# QXZ-v1_0.net
KiCad netlist of a schematic drawn in Altium Designer
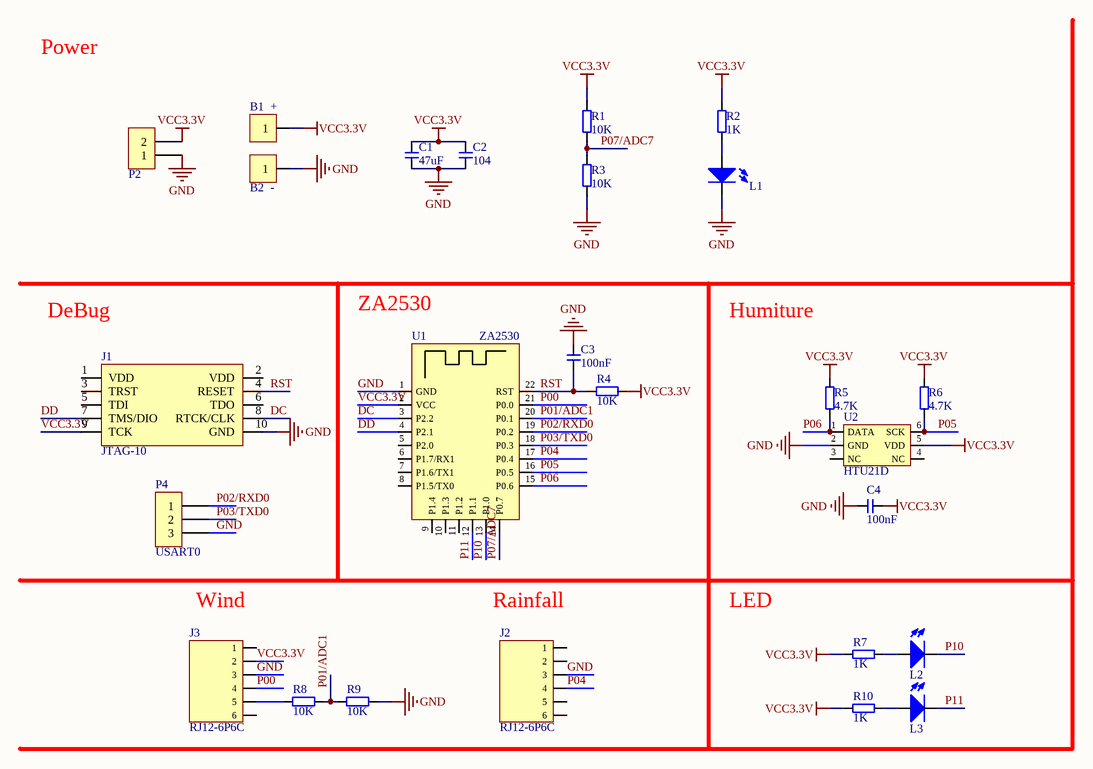
[diagram p0: QXZ-v1.0.SchDoc]

(export (version "E")
  (design (tool "Eeschema 10.0.6"))
  (components
    (comp (ref "B1")
      (value "+")
      (footprint "BatteryContacts-5#")
      (libsource (lib "集成库1") (part "BatteryContacts-5#"))
    )
    (comp (ref "B2")
      (value "-")
      (footprint "BatteryContacts-5#")
      (libsource (lib "集成库1") (part "BatteryContacts-5#"))
    )
    (comp (ref "C1") (value "47uF") (footprint "CAP(0805)") (libsource (lib "集成库1") (part "Cap0805")))
    (comp (ref "C2") (value "104") (footprint "CAP(0603)") (libsource (lib "集成库1") (part "Cap0603")))
    (comp (ref "C3") (value "100nF") (footprint "CAP(0603)") (libsource (lib "集成库1") (part "Cap0603")))
    (comp (ref "C4") (value "100nF") (footprint "CAP(0603)") (libsource (lib "集成库1") (part "Cap0603")))
    (comp (ref "J1") (value "JTAG-10") (footprint "JTAG-10") (libsource (lib "集成库1") (part "JTAG-10")))
    (comp (ref "J2")
      (value "RJ12-6P6C")
      (footprint "RJ12-6P6C-up")
      (libsource (lib "集成库1") (part "RJ12-6P6C-up"))
    )
    (comp (ref "J3")
      (value "RJ12-6P6C")
      (footprint "RJ12-6P6C-up")
      (libsource (lib "集成库1") (part "RJ12-6P6C-up"))
    )
    (comp (ref "L1") (value "LED") (footprint "led0805") (libsource (lib "集成库1") (part "LED0805")))
    (comp (ref "L2") (value "LED") (footprint "led0805") (libsource (lib "集成库1") (part "LED0805")))
    (comp (ref "L3") (value "LED") (footprint "led0805") (libsource (lib "集成库1") (part "LED0805")))
    (comp (ref "P2") (value "Header2") (footprint "Header2") (libsource (lib "集成库1") (part "Header2")))
    (comp (ref "P4") (value "USART0") (footprint "HEADER3") (libsource (lib "集成库1") (part "Header3")))
    (comp (ref "R1") (value "10K") (footprint "RES0603") (libsource (lib "集成库1") (part "RES0603")))
    (comp (ref "R2") (value "1K") (footprint "RES0603") (libsource (lib "集成库1") (part "RES0603")))
    (comp (ref "R3") (value "10K") (footprint "RES0603") (libsource (lib "集成库1") (part "RES0603")))
    (comp (ref "R4") (value "10K") (footprint "RES0603") (libsource (lib "") (part "RES0603_1")))
    (comp (ref "R5") (value "4.7K") (footprint "RES0603") (libsource (lib "集成库1") (part "RES0603")))
    (comp (ref "R6") (value "4.7K") (footprint "RES0603") (libsource (lib "集成库1") (part "RES0603")))
    (comp (ref "R7") (value "1K") (footprint "RES0603") (libsource (lib "") (part "RES0603_1")))
    (comp (ref "R8") (value "10K") (footprint "RES0603") (libsource (lib "") (part "RES0603_1")))
    (comp (ref "R9") (value "10K") (footprint "RES0603") (libsource (lib "") (part "RES0603_1")))
    (comp (ref "R10") (value "1K") (footprint "RES0603") (libsource (lib "") (part "RES0603_1")))
    (comp (ref "U1") (value "ZA2530") (footprint "ZA2530A") (libsource (lib "集成库1") (part "ZA2530A")))
    (comp (ref "U2") (value "HTU21D") (footprint "DFN6") (libsource (lib "集成库1") (part "htu21d")))
  )
  (nets
    (net (code "1") (name "/DC") (class "Default")
      (node (ref "J1") (pin "8") (pinfunction "RTCK/CLK_8") (pintype "passive"))
      (node (ref "U1") (pin "3") (pinfunction "P2.2_3") (pintype "passive"))
    )
    (net (code "2") (name "/DD") (class "Default")
      (node (ref "J1") (pin "7") (pinfunction "TMS/DIO_7") (pintype "passive"))
      (node (ref "U1") (pin "4") (pinfunction "P2.1_4") (pintype "passive"))
    )
    (net (code "3") (name "/P00") (class "Default")
      (node (ref "J3") (pin "4") (pinfunction "4_4") (pintype "passive"))
      (node (ref "U1") (pin "21") (pinfunction "P0.0_21") (pintype "passive"))
    )
    (net (code "4") (name "/P01{slash}ADC1") (class "Default")
      (node (ref "R8") (pin "2") (pinfunction "2_2") (pintype "passive"))
      (node (ref "R9") (pin "1") (pinfunction "1_1") (pintype "passive"))
      (node (ref "U1") (pin "20") (pinfunction "P0.1_20") (pintype "passive"))
    )
    (net (code "5") (name "/P02{slash}RXD0") (class "Default")
      (node (ref "P4") (pin "1") (pinfunction "1_1") (pintype "passive"))
      (node (ref "U1") (pin "19") (pinfunction "P0.2_19") (pintype "passive"))
    )
    (net (code "6") (name "/P03{slash}TXD0") (class "Default")
      (node (ref "P4") (pin "2") (pinfunction "2_2") (pintype "passive"))
      (node (ref "U1") (pin "18") (pinfunction "P0.3_18") (pintype "passive"))
    )
    (net (code "7") (name "/P04") (class "Default")
      (node (ref "J2") (pin "4") (pinfunction "4_4") (pintype "passive"))
      (node (ref "U1") (pin "17") (pinfunction "P0.4_17") (pintype "passive"))
    )
    (net (code "8") (name "/P05") (class "Default")
      (node (ref "R6") (pin "1") (pinfunction "1_1") (pintype "passive"))
      (node (ref "U1") (pin "16") (pinfunction "P0.5_16") (pintype "passive"))
      (node (ref "U2") (pin "6") (pinfunction "SCK_6") (pintype "passive"))
    )
    (net (code "9") (name "/P06") (class "Default")
      (node (ref "R5") (pin "1") (pinfunction "1_1") (pintype "passive"))
      (node (ref "U1") (pin "15") (pinfunction "P0.6_15") (pintype "passive"))
      (node (ref "U2") (pin "1") (pinfunction "DATA_1") (pintype "passive"))
    )
    (net (code "10") (name "/P07{slash}ADC7") (class "Default")
      (node (ref "R1") (pin "1") (pinfunction "1_1") (pintype "passive"))
      (node (ref "R3") (pin "2") (pinfunction "2_2") (pintype "passive"))
      (node (ref "U1") (pin "14") (pinfunction "P0.7_14") (pintype "passive"))
    )
    (net (code "11") (name "/P10") (class "Default")
      (node (ref "L2") (pin "2") (pinfunction "2_2") (pintype "passive"))
      (node (ref "U1") (pin "13") (pinfunction "P1.0_13") (pintype "passive"))
    )
    (net (code "12") (name "/P11") (class "Default")
      (node (ref "L3") (pin "2") (pinfunction "2_2") (pintype "passive"))
      (node (ref "U1") (pin "12") (pinfunction "P1.1_12") (pintype "passive"))
    )
    (net (code "13") (name "/RST") (class "Default")
      (node (ref "C3") (pin "1") (pinfunction "1_1") (pintype "passive"))
      (node (ref "J1") (pin "4") (pinfunction "RESET_4") (pintype "passive"))
      (node (ref "R4") (pin "1") (pinfunction "1_1") (pintype "passive"))
      (node (ref "U1") (pin "22") (pinfunction "RST_22") (pintype "passive"))
    )
    (net (code "14") (name "GND") (class "Default")
      (node (ref "B2") (pin "1") (pinfunction "1_1") (pintype "passive"))
      (node (ref "C1") (pin "1") (pinfunction "1_1") (pintype "passive"))
      (node (ref "C2") (pin "1") (pinfunction "1_1") (pintype "passive"))
      (node (ref "C3") (pin "2") (pinfunction "2_2") (pintype "passive"))
      (node (ref "C4") (pin "1") (pinfunction "1_1") (pintype "passive"))
      (node (ref "J1") (pin "10") (pinfunction "GND_10") (pintype "passive"))
      (node (ref "J2") (pin "3") (pinfunction "3_3") (pintype "passive"))
      (node (ref "J3") (pin "3") (pinfunction "3_3") (pintype "passive"))
      (node (ref "L1") (pin "2") (pinfunction "2_2") (pintype "passive"))
      (node (ref "P2") (pin "1") (pinfunction "1_1") (pintype "passive"))
      (node (ref "P4") (pin "3") (pinfunction "3_3") (pintype "passive"))
      (node (ref "R3") (pin "1") (pinfunction "1_1") (pintype "passive"))
      (node (ref "R9") (pin "2") (pinfunction "2_2") (pintype "passive"))
      (node (ref "U1") (pin "1") (pinfunction "GND_1") (pintype "passive"))
      (node (ref "U2") (pin "2") (pinfunction "GND_2") (pintype "passive"))
    )
    (net (code "15") (name "Net-(J3-Pad5)") (class "Default")
      (node (ref "J3") (pin "5") (pinfunction "5_5") (pintype "passive"))
      (node (ref "R8") (pin "1") (pinfunction "1_1") (pintype "passive"))
    )
    (net (code "16") (name "Net-(L1-Pad1)") (class "Default")
      (node (ref "L1") (pin "1") (pinfunction "1_1") (pintype "passive"))
      (node (ref "R2") (pin "1") (pinfunction "1_1") (pintype "passive"))
    )
    (net (code "17") (name "Net-(L2-Pad1)") (class "Default")
      (node (ref "L2") (pin "1") (pinfunction "1_1") (pintype "passive"))
      (node (ref "R7") (pin "2") (pinfunction "2_2") (pintype "passive"))
    )
    (net (code "18") (name "Net-(L3-Pad1)") (class "Default")
      (node (ref "L3") (pin "1") (pinfunction "1_1") (pintype "passive"))
      (node (ref "R10") (pin "2") (pinfunction "2_2") (pintype "passive"))
    )
    (net (code "19") (name "VCC3.3V") (class "Default")
      (node (ref "B1") (pin "1") (pinfunction "1_1") (pintype "passive"))
      (node (ref "C1") (pin "2") (pinfunction "2_2") (pintype "passive"))
      (node (ref "C2") (pin "2") (pinfunction "2_2") (pintype "passive"))
      (node (ref "C4") (pin "2") (pinfunction "2_2") (pintype "passive"))
      (node (ref "J1") (pin "9") (pinfunction "TCK_9") (pintype "passive"))
      (node (ref "J3") (pin "2") (pinfunction "2_2") (pintype "passive"))
      (node (ref "P2") (pin "2") (pinfunction "2_2") (pintype "passive"))
      (node (ref "R1") (pin "2") (pinfunction "2_2") (pintype "passive"))
      (node (ref "R10") (pin "1") (pinfunction "1_1") (pintype "passive"))
      (node (ref "R2") (pin "2") (pinfunction "2_2") (pintype "passive"))
      (node (ref "R4") (pin "2") (pinfunction "2_2") (pintype "passive"))
      (node (ref "R5") (pin "2") (pinfunction "2_2") (pintype "passive"))
      (node (ref "R6") (pin "2") (pinfunction "2_2") (pintype "passive"))
      (node (ref "R7") (pin "1") (pinfunction "1_1") (pintype "passive"))
      (node (ref "U1") (pin "2") (pinfunction "VCC_2") (pintype "passive"))
      (node (ref "U2") (pin "5") (pinfunction "VDD_5") (pintype "passive"))
    )
    (net (code "20") (name "unconnected-(J1-TDI-Pad5)") (class "Default")
      (node (ref "J1") (pin "5") (pinfunction "TDI_5") (pintype "passive"))
    )
    (net (code "21") (name "unconnected-(J1-TDO-Pad6)") (class "Default")
      (node (ref "J1") (pin "6") (pinfunction "TDO_6") (pintype "passive"))
    )
    (net (code "22") (name "unconnected-(J1-TRST-Pad3)") (class "Default")
      (node (ref "J1") (pin "3") (pinfunction "TRST_3") (pintype "passive"))
    )
    (net (code "23") (name "unconnected-(J1-VDD-Pad1)") (class "Default")
      (node (ref "J1") (pin "1") (pinfunction "VDD_1") (pintype "passive"))
    )
    (net (code "24") (name "unconnected-(J1-VDD-Pad2)") (class "Default")
      (node (ref "J1") (pin "2") (pinfunction "VDD_2") (pintype "passive"))
    )
    (net (code "25") (name "unconnected-(J2-Pad1)") (class "Default")
      (node (ref "J2") (pin "1") (pinfunction "1_1") (pintype "passive"))
    )
    (net (code "26") (name "unconnected-(J2-Pad2)") (class "Default")
      (node (ref "J2") (pin "2") (pinfunction "2_2") (pintype "passive"))
    )
    (net (code "27") (name "unconnected-(J2-Pad5)") (class "Default")
      (node (ref "J2") (pin "5") (pinfunction "5_5") (pintype "passive"))
    )
    (net (code "28") (name "unconnected-(J2-Pad6)") (class "Default")
      (node (ref "J2") (pin "6") (pinfunction "6_6") (pintype "passive"))
    )
    (net (code "29") (name "unconnected-(J3-Pad1)") (class "Default")
      (node (ref "J3") (pin "1") (pinfunction "1_1") (pintype "passive"))
    )
    (net (code "30") (name "unconnected-(J3-Pad6)") (class "Default")
      (node (ref "J3") (pin "6") (pinfunction "6_6") (pintype "passive"))
    )
    (net (code "31") (name "unconnected-(U1-P1.2-Pad11)") (class "Default")
      (node (ref "U1") (pin "11") (pinfunction "P1.2_11") (pintype "passive"))
    )
    (net (code "32") (name "unconnected-(U1-P1.3-Pad10)") (class "Default")
      (node (ref "U1") (pin "10") (pinfunction "P1.3_10") (pintype "passive"))
    )
    (net (code "33") (name "unconnected-(U1-P1.4-Pad9)") (class "Default")
      (node (ref "U1") (pin "9") (pinfunction "P1.4_9") (pintype "passive"))
    )
    (net (code "34") (name "unconnected-(U1-P1.5{slash}TX0-Pad8)") (class "Default")
      (node (ref "U1") (pin "8") (pinfunction "P1.5/TX0_8") (pintype "passive"))
    )
    (net (code "35") (name "unconnected-(U1-P1.6{slash}TX1-Pad7)") (class "Default")
      (node (ref "U1") (pin "7") (pinfunction "P1.6/TX1_7") (pintype "passive"))
    )
    (net (code "36") (name "unconnected-(U1-P1.7{slash}RX1-Pad6)") (class "Default")
      (node (ref "U1") (pin "6") (pinfunction "P1.7/RX1_6") (pintype "passive"))
    )
    (net (code "37") (name "unconnected-(U1-P2.0-Pad5)") (class "Default")
      (node (ref "U1") (pin "5") (pinfunction "P2.0_5") (pintype "passive"))
    )
    (net (code "38") (name "unconnected-(U2-NC-Pad3)") (class "Default")
      (node (ref "U2") (pin "3") (pinfunction "NC_3") (pintype "passive"))
    )
    (net (code "39") (name "unconnected-(U2-NC-Pad4)") (class "Default")
      (node (ref "U2") (pin "4") (pinfunction "NC_4") (pintype "passive"))
    )
  )
)
